# Motor.net
KiCad netlist of a schematic drawn in Altium Designer
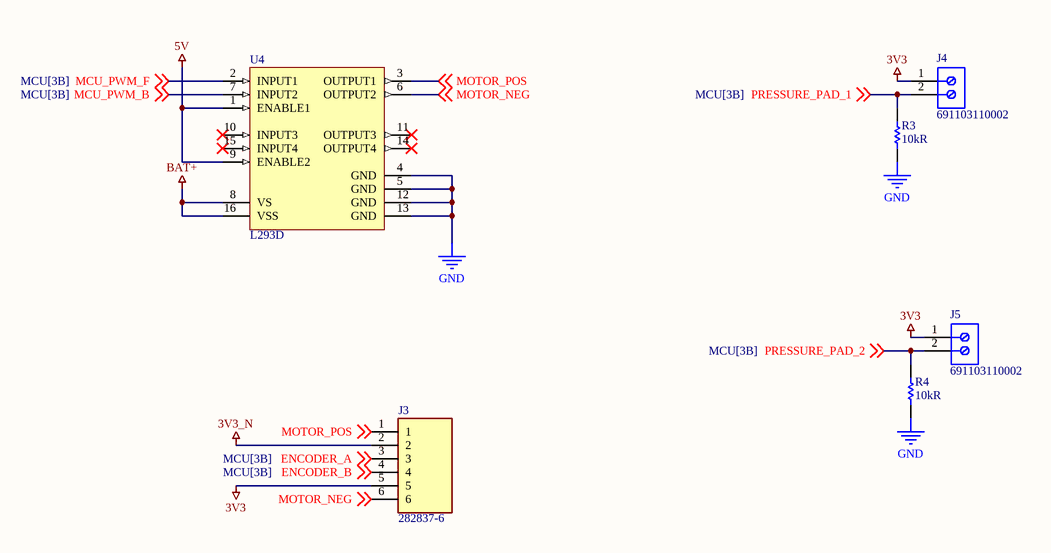
[diagram p0: Motor.SchDoc]

(export (version "E")
  (design (tool "Eeschema 10.0.6"))
  (components
    (comp (ref "J3")
      (value "282837-6")
      (footprint "SamacSys:2828376")
      (description "Connector")
      (fields (field (name "MOUSER PART NUMBER") "571-2828376"))
      (libsource (lib "*") (part "282837-6"))
    )
    (comp (ref "J4")
      (value "691103110002")
      (footprint "691103110002")
      (fields (field (name "VOLTAGE") "125V"))
      (libsource (lib "Altium Content Vault") (part "TBL - 1R - 02P - Screw"))
    )
    (comp (ref "J5")
      (value "691103110002")
      (footprint "691103110002")
      (fields (field (name "VOLTAGE") "125V"))
      (libsource (lib "Altium Content Vault") (part "TBL - 1R - 02P - Screw"))
    )
    (comp (ref "R3")
      (value "10kR")
      (footprint "RESC2013X60X35NL10T20")
      (description "Chip Resistor, 10 KOhm, +/- 1%, 0.125 W, -55 to 155 degC, 0805 (2012 Metric), RoHS, Tape and Reel")
      (fields
        (field (name "MANUFACTURER") "Yageo")
        (field (name "MANUFACTURER PART NUMBER") "RC0805FR-0710KL")
      )
      (libsource (lib "Altium Content Vault") (part "RES-2"))
    )
    (comp (ref "R4")
      (value "10kR")
      (footprint "RESC2013X60X35NL10T20")
      (description "Chip Resistor, 10 KOhm, +/- 1%, 0.125 W, -55 to 155 degC, 0805 (2012 Metric), RoHS, Tape and Reel")
      (fields
        (field (name "MANUFACTURER") "Yageo")
        (field (name "MANUFACTURER PART NUMBER") "RC0805FR-0710KL")
      )
      (libsource (lib "Altium Content Vault") (part "RES-2"))
    )
    (comp (ref "U4")
      (value "L293D")
      (footprint "STM-L293D-16")
      (description "Push-Pull Four Channel Driver with Diode, 4.5 to 36 V, -40 to 150 degC, 16-Pin PDIP, RoHS, Tube")
      (fields (field (name "MANUFACTURER") "STMicroelectronics"))
      (libsource (lib "Altium Content Vault") (part "STM-L293D-16"))
    )
  )
  (nets
    (net (code "1") (name "3V3") (class "Default")
      (node (ref "J3") (pin "5") (pinfunction "5_5") (pintype "passive"))
      (node (ref "J4") (pin "1") (pinfunction "1_1") (pintype "passive"))
      (node (ref "J5") (pin "1") (pinfunction "1_1") (pintype "passive"))
    )
    (net (code "2") (name "3V3_N") (class "Default")
      (node (ref "J3") (pin "2") (pinfunction "2_2") (pintype "passive"))
    )
    (net (code "3") (name "5V") (class "Default")
      (node (ref "U4") (pin "1") (pinfunction "ENABLE1_1") (pintype "input"))
      (node (ref "U4") (pin "9") (pinfunction "ENABLE2_9") (pintype "input"))
    )
    (net (code "4") (name "BAT+") (class "Default")
      (node (ref "U4") (pin "16") (pinfunction "VSS_16") (pintype "power_in"))
      (node (ref "U4") (pin "8") (pinfunction "VS_8") (pintype "power_in"))
    )
    (net (code "5") (name "ENCODER_A") (class "Default")
      (node (ref "J3") (pin "3") (pinfunction "3_3") (pintype "passive"))
    )
    (net (code "6") (name "ENCODER_B") (class "Default")
      (node (ref "J3") (pin "4") (pinfunction "4_4") (pintype "passive"))
    )
    (net (code "7") (name "GND") (class "Default")
      (node (ref "R3") (pin "2") (pinfunction "2_2") (pintype "passive"))
      (node (ref "R4") (pin "2") (pinfunction "2_2") (pintype "passive"))
      (node (ref "U4") (pin "12") (pinfunction "GND_12") (pintype "power_in"))
      (node (ref "U4") (pin "13") (pinfunction "GND_13") (pintype "power_in"))
      (node (ref "U4") (pin "4") (pinfunction "GND_4") (pintype "power_in"))
      (node (ref "U4") (pin "5") (pinfunction "GND_5") (pintype "power_in"))
    )
    (net (code "8") (name "MCU_PWM_B") (class "Default")
      (node (ref "U4") (pin "7") (pinfunction "INPUT2_7") (pintype "input"))
    )
    (net (code "9") (name "MCU_PWM_F") (class "Default")
      (node (ref "U4") (pin "2") (pinfunction "INPUT1_2") (pintype "input"))
    )
    (net (code "10") (name "MOTOR_NEG") (class "Default")
      (node (ref "J3") (pin "6") (pinfunction "6_6") (pintype "passive"))
      (node (ref "U4") (pin "6") (pinfunction "OUTPUT2_6") (pintype "output"))
    )
    (net (code "11") (name "MOTOR_POS") (class "Default")
      (node (ref "J3") (pin "1") (pinfunction "1_1") (pintype "passive"))
      (node (ref "U4") (pin "3") (pinfunction "OUTPUT1_3") (pintype "output"))
    )
    (net (code "12") (name "PRESSURE_PAD_1") (class "Default")
      (node (ref "J4") (pin "2") (pinfunction "2_2") (pintype "passive"))
      (node (ref "R3") (pin "1") (pinfunction "1_1") (pintype "passive"))
    )
    (net (code "13") (name "PRESSURE_PAD_2") (class "Default")
      (node (ref "J5") (pin "2") (pinfunction "2_2") (pintype "passive"))
      (node (ref "R4") (pin "1") (pinfunction "1_1") (pintype "passive"))
    )
    (net (code "14") (name "unconnected-(U4-INPUT3-Pad10)") (class "Default")
      (node (ref "U4") (pin "10") (pinfunction "INPUT3_10") (pintype "input+no_connect"))
    )
    (net (code "15") (name "unconnected-(U4-INPUT4-Pad15)") (class "Default")
      (node (ref "U4") (pin "15") (pinfunction "INPUT4_15") (pintype "input+no_connect"))
    )
    (net (code "16") (name "unconnected-(U4-OUTPUT3-Pad11)") (class "Default")
      (node (ref "U4") (pin "11") (pinfunction "OUTPUT3_11") (pintype "output+no_connect"))
    )
    (net (code "17") (name "unconnected-(U4-OUTPUT4-Pad14)") (class "Default")
      (node (ref "U4") (pin "14") (pinfunction "OUTPUT4_14") (pintype "output+no_connect"))
    )
  )
)
